# Proto_shield_REV3.net
KiCad netlist of a schematic drawn in EAGLE
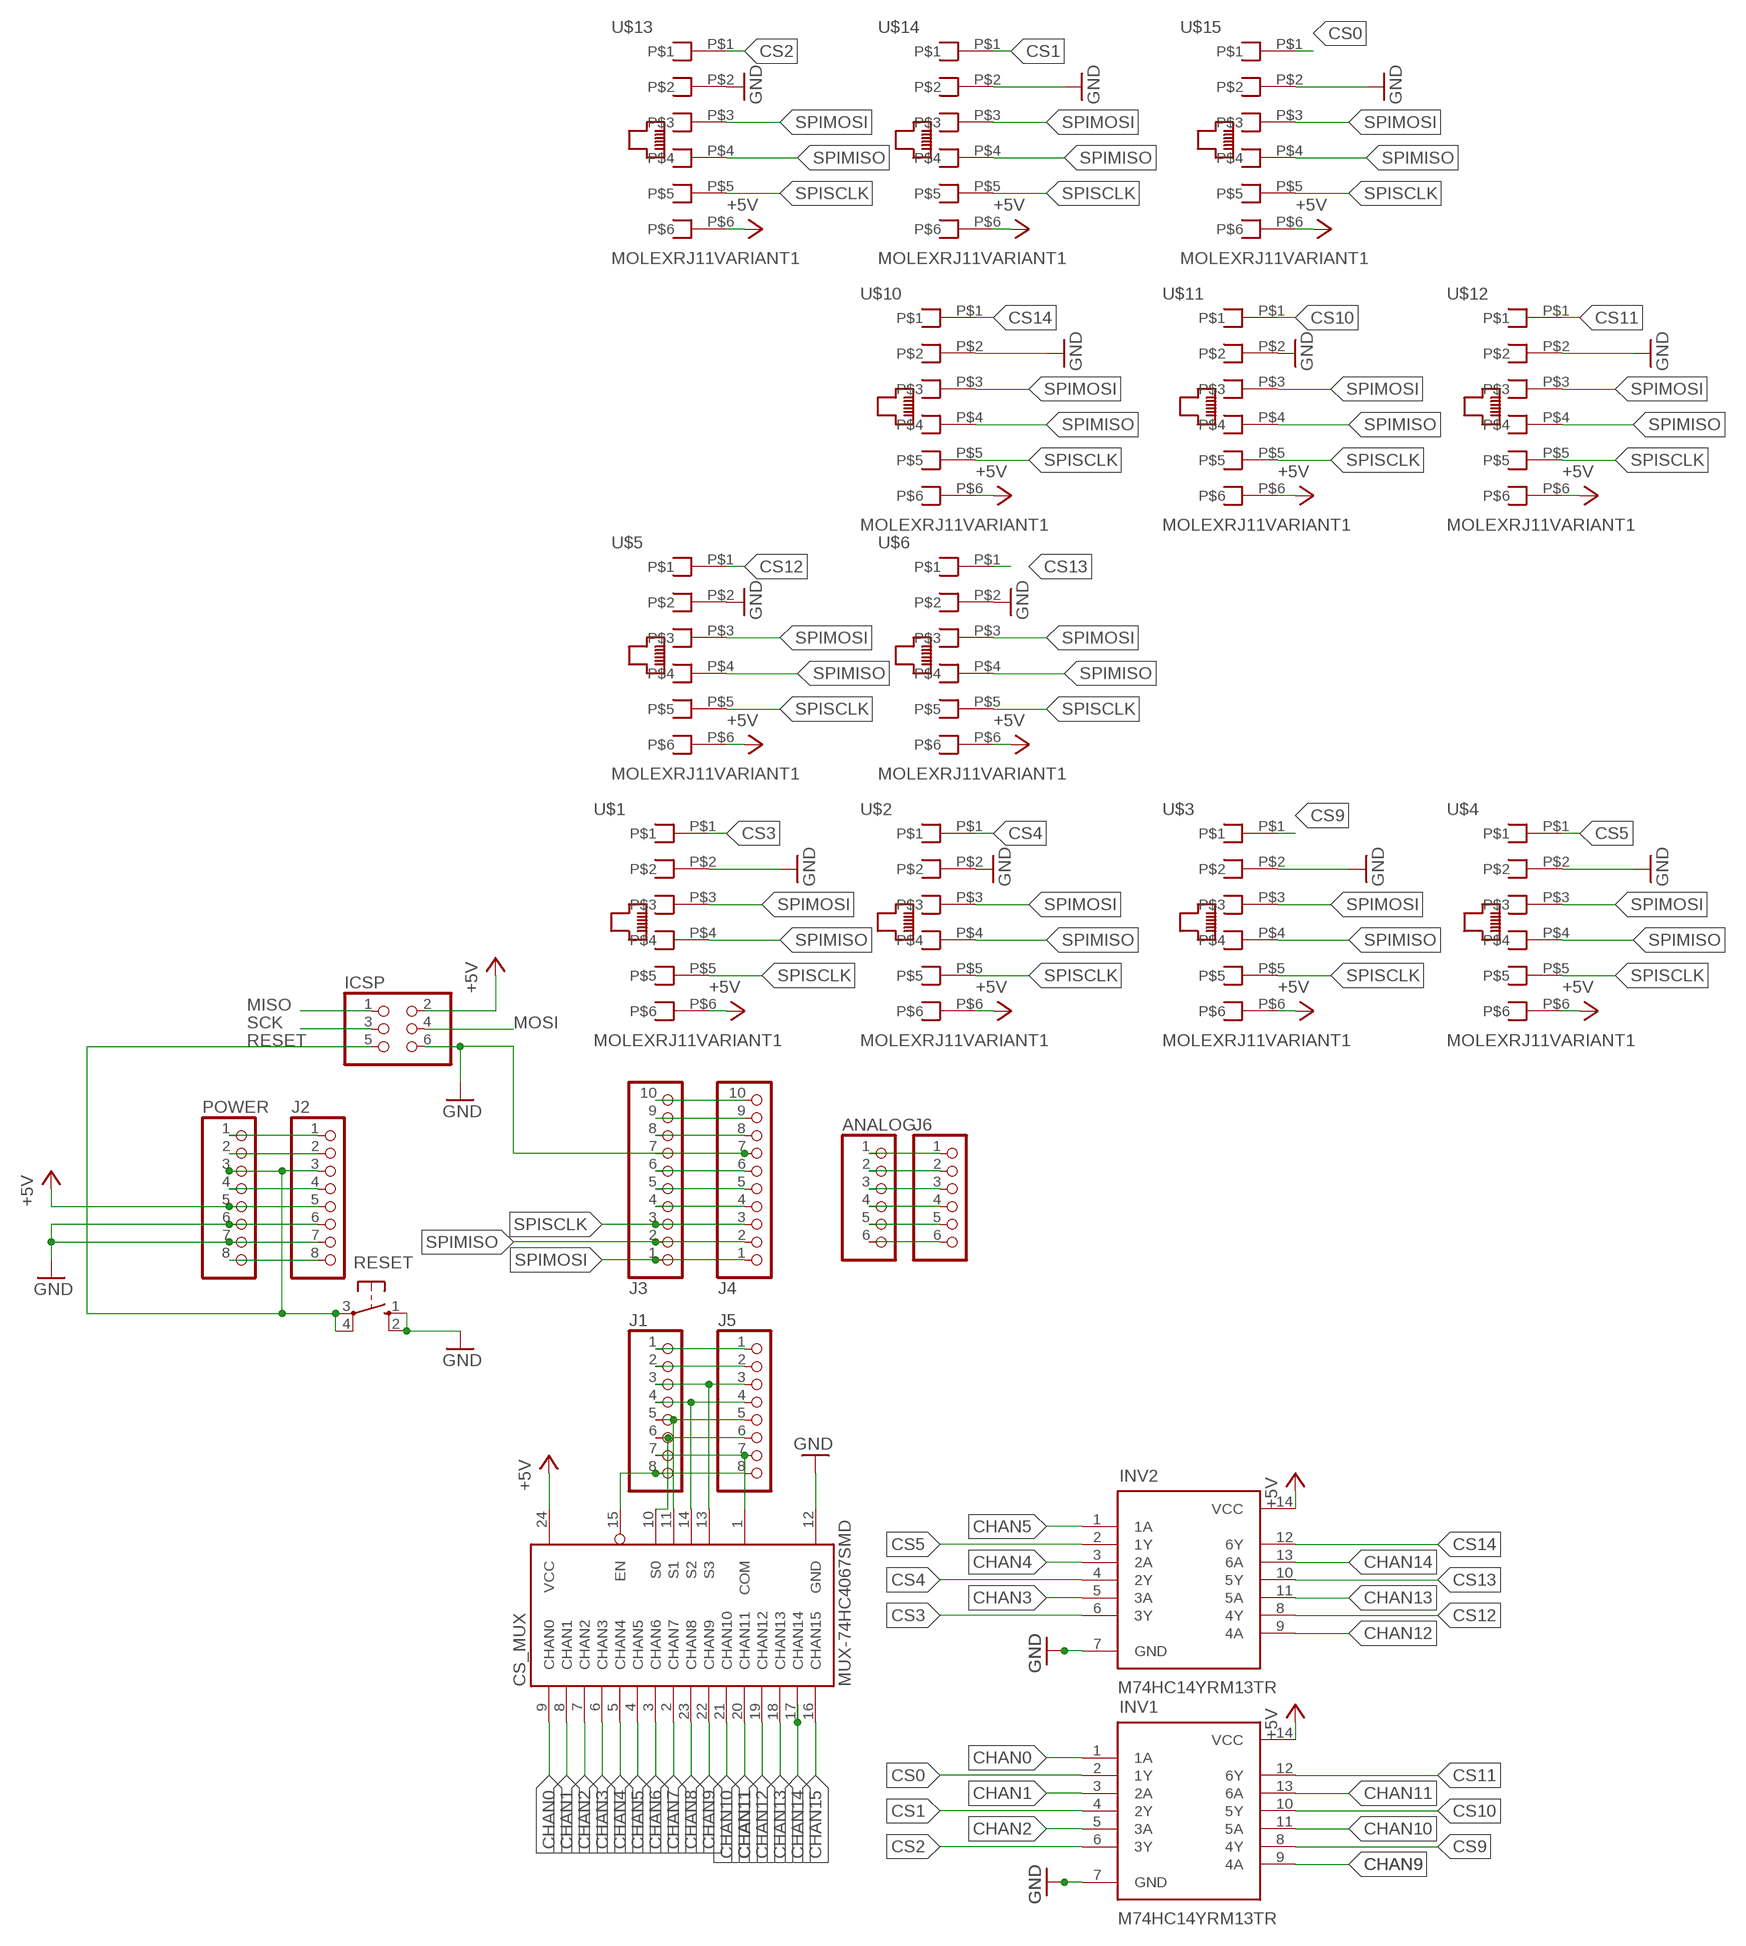
[diagram p0: schematic, sheet 1]

(export (version "E")
  (design (tool "Eeschema 10.0.6"))
  (components
    (comp (ref "ANALOG")
      (value "PINHD-1X6")
      (footprint "eagle-import:1X06")
      (libsource (lib "eagle-import") (part "PINHD-1X6"))
    )
    (comp (ref "CS_MUX")
      (value "MUX-74HC4067SMD")
      (footprint "eagle-import:SSOP24")
      (libsource (lib "eagle-import") (part "MUX-74HC4067SMD"))
    )
    (comp (ref "ICSP")
      (value "PINHD-2X3")
      (footprint "eagle-import:2X03")
      (libsource (lib "eagle-import") (part "PINHD-2X3"))
    )
    (comp (ref "INV1")
      (value "M74HC14YRM13TR")
      (footprint "eagle-import:SO14")
      (libsource (lib "eagle-import") (part "M74HC14YRM13TR"))
    )
    (comp (ref "INV2")
      (value "M74HC14YRM13TR")
      (footprint "eagle-import:SO14")
      (libsource (lib "eagle-import") (part "M74HC14YRM13TR"))
    )
    (comp (ref "J1")
      (value "PINHD-1X8TH")
      (footprint "eagle-import:1X08-TH")
      (libsource (lib "eagle-import") (part "PINHD-1X8TH"))
    )
    (comp (ref "J2")
      (value "PINHD-1X8TH")
      (footprint "eagle-import:1X08-TH")
      (libsource (lib "eagle-import") (part "PINHD-1X8TH"))
    )
    (comp (ref "J3")
      (value "PINHD-1X10TH")
      (footprint "eagle-import:1X10-TH")
      (libsource (lib "eagle-import") (part "PINHD-1X10TH"))
    )
    (comp (ref "J4")
      (value "PINHD-1X10TH")
      (footprint "eagle-import:1X10-TH")
      (libsource (lib "eagle-import") (part "PINHD-1X10TH"))
    )
    (comp (ref "J5")
      (value "PINHD-1X8TH")
      (footprint "eagle-import:1X08-TH")
      (libsource (lib "eagle-import") (part "PINHD-1X8TH"))
    )
    (comp (ref "J6")
      (value "PINHD-1X6")
      (footprint "eagle-import:1X06")
      (libsource (lib "eagle-import") (part "PINHD-1X6"))
    )
    (comp (ref "POWER")
      (value "PINHD-1X8TH")
      (footprint "eagle-import:1X08-TH")
      (libsource (lib "eagle-import") (part "PINHD-1X8TH"))
    )
    (comp (ref "RESET")
      (value "10-XX")
      (footprint "eagle-import:B3F-10XX")
      (libsource (lib "eagle-import") (part "10-XX"))
    )
    (comp (ref "U$1")
      (value "MOLEXRJ11VARIANT1")
      (footprint "eagle-import:RJ11MOLEX")
      (libsource (lib "eagle-import") (part "MOLEXRJ11VARIANT1"))
    )
    (comp (ref "U$2")
      (value "MOLEXRJ11VARIANT1")
      (footprint "eagle-import:RJ11MOLEX")
      (libsource (lib "eagle-import") (part "MOLEXRJ11VARIANT1"))
    )
    (comp (ref "U$3")
      (value "MOLEXRJ11VARIANT1")
      (footprint "eagle-import:RJ11MOLEX")
      (libsource (lib "eagle-import") (part "MOLEXRJ11VARIANT1"))
    )
    (comp (ref "U$4")
      (value "MOLEXRJ11VARIANT1")
      (footprint "eagle-import:RJ11MOLEX")
      (libsource (lib "eagle-import") (part "MOLEXRJ11VARIANT1"))
    )
    (comp (ref "U$5")
      (value "MOLEXRJ11VARIANT1")
      (footprint "eagle-import:RJ11MOLEX")
      (libsource (lib "eagle-import") (part "MOLEXRJ11VARIANT1"))
    )
    (comp (ref "U$6")
      (value "MOLEXRJ11VARIANT1")
      (footprint "eagle-import:RJ11MOLEX")
      (libsource (lib "eagle-import") (part "MOLEXRJ11VARIANT1"))
    )
    (comp (ref "U$10")
      (value "MOLEXRJ11VARIANT1")
      (footprint "eagle-import:RJ11MOLEX")
      (libsource (lib "eagle-import") (part "MOLEXRJ11VARIANT1"))
    )
    (comp (ref "U$11")
      (value "MOLEXRJ11VARIANT1")
      (footprint "eagle-import:RJ11MOLEX")
      (libsource (lib "eagle-import") (part "MOLEXRJ11VARIANT1"))
    )
    (comp (ref "U$12")
      (value "MOLEXRJ11VARIANT1")
      (footprint "eagle-import:RJ11MOLEX")
      (libsource (lib "eagle-import") (part "MOLEXRJ11VARIANT1"))
    )
    (comp (ref "U$13")
      (value "MOLEXRJ11VARIANT1")
      (footprint "eagle-import:RJ11MOLEX")
      (libsource (lib "eagle-import") (part "MOLEXRJ11VARIANT1"))
    )
    (comp (ref "U$14")
      (value "MOLEXRJ11VARIANT1")
      (footprint "eagle-import:RJ11MOLEX")
      (libsource (lib "eagle-import") (part "MOLEXRJ11VARIANT1"))
    )
    (comp (ref "U$15")
      (value "MOLEXRJ11VARIANT1")
      (footprint "eagle-import:RJ11MOLEX")
      (libsource (lib "eagle-import") (part "MOLEXRJ11VARIANT1"))
    )
  )
  (nets
    (net (code "1") (name "+5V") (class "Default")
      (node (ref "CS_MUX") (pin "24") (pinfunction "VCC_24") (pintype "bidirectional"))
      (node (ref "ICSP") (pin "2") (pinfunction "2_2") (pintype "passive"))
      (node (ref "INV1") (pin "14") (pinfunction "VCC_14") (pintype "bidirectional"))
      (node (ref "INV2") (pin "14") (pinfunction "VCC_14") (pintype "bidirectional"))
      (node (ref "J2") (pin "5") (pinfunction "5_5") (pintype "passive"))
      (node (ref "POWER") (pin "5") (pinfunction "5_5") (pintype "passive"))
      (node (ref "U$1") (pin "P$6") (pinfunction "P$6_P$6") (pintype "bidirectional"))
      (node (ref "U$10") (pin "P$6") (pinfunction "P$6_P$6") (pintype "bidirectional"))
      (node (ref "U$11") (pin "P$6") (pinfunction "P$6_P$6") (pintype "bidirectional"))
      (node (ref "U$12") (pin "P$6") (pinfunction "P$6_P$6") (pintype "bidirectional"))
      (node (ref "U$13") (pin "P$6") (pinfunction "P$6_P$6") (pintype "bidirectional"))
      (node (ref "U$14") (pin "P$6") (pinfunction "P$6_P$6") (pintype "bidirectional"))
      (node (ref "U$15") (pin "P$6") (pinfunction "P$6_P$6") (pintype "bidirectional"))
      (node (ref "U$2") (pin "P$6") (pinfunction "P$6_P$6") (pintype "bidirectional"))
      (node (ref "U$3") (pin "P$6") (pinfunction "P$6_P$6") (pintype "bidirectional"))
      (node (ref "U$4") (pin "P$6") (pinfunction "P$6_P$6") (pintype "bidirectional"))
      (node (ref "U$5") (pin "P$6") (pinfunction "P$6_P$6") (pintype "bidirectional"))
      (node (ref "U$6") (pin "P$6") (pinfunction "P$6_P$6") (pintype "bidirectional"))
    )
    (net (code "2") (name "/MISO") (class "Default")
      (node (ref "ICSP") (pin "1") (pinfunction "1_1") (pintype "passive"))
    )
    (net (code "3") (name "/MOSI") (class "Default")
      (node (ref "ICSP") (pin "4") (pinfunction "4_4") (pintype "passive"))
    )
    (net (code "4") (name "/RESET") (class "Default")
      (node (ref "ICSP") (pin "5") (pinfunction "5_5") (pintype "passive"))
      (node (ref "J2") (pin "3") (pinfunction "3_3") (pintype "passive"))
      (node (ref "POWER") (pin "3") (pinfunction "3_3") (pintype "passive"))
      (node (ref "RESET") (pin "3") (pinfunction "P_3") (pintype "passive"))
      (node (ref "RESET") (pin "4") (pinfunction "P1_4") (pintype "passive"))
    )
    (net (code "5") (name "/SCK") (class "Default")
      (node (ref "ICSP") (pin "3") (pinfunction "3_3") (pintype "passive"))
    )
    (net (code "6") (name "CHAN0") (class "Default")
      (node (ref "CS_MUX") (pin "9") (pinfunction "CHAN0_9") (pintype "bidirectional"))
      (node (ref "INV1") (pin "1") (pinfunction "1A_1") (pintype "bidirectional"))
    )
    (net (code "7") (name "CHAN1") (class "Default")
      (node (ref "CS_MUX") (pin "8") (pinfunction "CHAN1_8") (pintype "bidirectional"))
      (node (ref "INV1") (pin "3") (pinfunction "2A_3") (pintype "bidirectional"))
    )
    (net (code "8") (name "CHAN2") (class "Default")
      (node (ref "CS_MUX") (pin "7") (pinfunction "CHAN2_7") (pintype "bidirectional"))
      (node (ref "INV1") (pin "5") (pinfunction "3A_5") (pintype "bidirectional"))
    )
    (net (code "9") (name "CHAN3") (class "Default")
      (node (ref "CS_MUX") (pin "6") (pinfunction "CHAN3_6") (pintype "bidirectional"))
      (node (ref "INV2") (pin "5") (pinfunction "3A_5") (pintype "bidirectional"))
    )
    (net (code "10") (name "CHAN4") (class "Default")
      (node (ref "CS_MUX") (pin "5") (pinfunction "CHAN4_5") (pintype "bidirectional"))
      (node (ref "INV2") (pin "3") (pinfunction "2A_3") (pintype "bidirectional"))
    )
    (net (code "11") (name "CHAN5") (class "Default")
      (node (ref "CS_MUX") (pin "4") (pinfunction "CHAN5_4") (pintype "bidirectional"))
      (node (ref "INV2") (pin "1") (pinfunction "1A_1") (pintype "bidirectional"))
    )
    (net (code "12") (name "CHAN6") (class "Default")
      (node (ref "CS_MUX") (pin "3") (pinfunction "CHAN6_3") (pintype "bidirectional"))
    )
    (net (code "13") (name "CHAN7") (class "Default")
      (node (ref "CS_MUX") (pin "2") (pinfunction "CHAN7_2") (pintype "bidirectional"))
    )
    (net (code "14") (name "CHAN8") (class "Default")
      (node (ref "CS_MUX") (pin "23") (pinfunction "CHAN8_23") (pintype "bidirectional"))
    )
    (net (code "15") (name "CHAN9") (class "Default")
      (node (ref "CS_MUX") (pin "22") (pinfunction "CHAN9_22") (pintype "bidirectional"))
      (node (ref "INV1") (pin "9") (pinfunction "4A_9") (pintype "bidirectional"))
    )
    (net (code "16") (name "CHAN10") (class "Default")
      (node (ref "CS_MUX") (pin "21") (pinfunction "CHAN10_21") (pintype "bidirectional"))
      (node (ref "INV1") (pin "11") (pinfunction "5A_11") (pintype "bidirectional"))
    )
    (net (code "17") (name "CHAN11") (class "Default")
      (node (ref "CS_MUX") (pin "20") (pinfunction "CHAN11_20") (pintype "bidirectional"))
      (node (ref "INV1") (pin "13") (pinfunction "6A_13") (pintype "bidirectional"))
    )
    (net (code "18") (name "CHAN12") (class "Default")
      (node (ref "CS_MUX") (pin "19") (pinfunction "CHAN12_19") (pintype "bidirectional"))
      (node (ref "INV2") (pin "9") (pinfunction "4A_9") (pintype "bidirectional"))
    )
    (net (code "19") (name "CHAN13") (class "Default")
      (node (ref "CS_MUX") (pin "18") (pinfunction "CHAN13_18") (pintype "bidirectional"))
      (node (ref "INV2") (pin "11") (pinfunction "5A_11") (pintype "bidirectional"))
    )
    (net (code "20") (name "CHAN14") (class "Default")
      (node (ref "CS_MUX") (pin "17") (pinfunction "CHAN14_17") (pintype "bidirectional"))
      (node (ref "INV2") (pin "13") (pinfunction "6A_13") (pintype "bidirectional"))
    )
    (net (code "21") (name "CHAN15") (class "Default")
      (node (ref "CS_MUX") (pin "16") (pinfunction "CHAN15_16") (pintype "bidirectional"))
    )
    (net (code "22") (name "CS0") (class "Default")
      (node (ref "INV1") (pin "2") (pinfunction "1Y_2") (pintype "bidirectional"))
      (node (ref "U$15") (pin "P$1") (pinfunction "P$1_P$1") (pintype "bidirectional"))
    )
    (net (code "23") (name "CS1") (class "Default")
      (node (ref "INV1") (pin "4") (pinfunction "2Y_4") (pintype "bidirectional"))
      (node (ref "U$14") (pin "P$1") (pinfunction "P$1_P$1") (pintype "bidirectional"))
    )
    (net (code "24") (name "CS2") (class "Default")
      (node (ref "INV1") (pin "6") (pinfunction "3Y_6") (pintype "bidirectional"))
      (node (ref "U$13") (pin "P$1") (pinfunction "P$1_P$1") (pintype "bidirectional"))
    )
    (net (code "25") (name "CS3") (class "Default")
      (node (ref "INV2") (pin "6") (pinfunction "3Y_6") (pintype "bidirectional"))
      (node (ref "U$1") (pin "P$1") (pinfunction "P$1_P$1") (pintype "bidirectional"))
    )
    (net (code "26") (name "CS4") (class "Default")
      (node (ref "INV2") (pin "4") (pinfunction "2Y_4") (pintype "bidirectional"))
      (node (ref "U$2") (pin "P$1") (pinfunction "P$1_P$1") (pintype "bidirectional"))
    )
    (net (code "27") (name "CS5") (class "Default")
      (node (ref "INV2") (pin "2") (pinfunction "1Y_2") (pintype "bidirectional"))
      (node (ref "U$4") (pin "P$1") (pinfunction "P$1_P$1") (pintype "bidirectional"))
    )
    (net (code "28") (name "CS9") (class "Default")
      (node (ref "INV1") (pin "8") (pinfunction "4Y_8") (pintype "bidirectional"))
      (node (ref "U$3") (pin "P$1") (pinfunction "P$1_P$1") (pintype "bidirectional"))
    )
    (net (code "29") (name "CS10") (class "Default")
      (node (ref "INV1") (pin "10") (pinfunction "5Y_10") (pintype "bidirectional"))
      (node (ref "U$11") (pin "P$1") (pinfunction "P$1_P$1") (pintype "bidirectional"))
    )
    (net (code "30") (name "CS11") (class "Default")
      (node (ref "INV1") (pin "12") (pinfunction "6Y_12") (pintype "bidirectional"))
      (node (ref "U$12") (pin "P$1") (pinfunction "P$1_P$1") (pintype "bidirectional"))
    )
    (net (code "31") (name "CS12") (class "Default")
      (node (ref "INV2") (pin "8") (pinfunction "4Y_8") (pintype "bidirectional"))
      (node (ref "U$5") (pin "P$1") (pinfunction "P$1_P$1") (pintype "bidirectional"))
    )
    (net (code "32") (name "CS13") (class "Default")
      (node (ref "INV2") (pin "10") (pinfunction "5Y_10") (pintype "bidirectional"))
      (node (ref "U$6") (pin "P$1") (pinfunction "P$1_P$1") (pintype "bidirectional"))
    )
    (net (code "33") (name "CS14") (class "Default")
      (node (ref "INV2") (pin "12") (pinfunction "6Y_12") (pintype "bidirectional"))
      (node (ref "U$10") (pin "P$1") (pinfunction "P$1_P$1") (pintype "bidirectional"))
    )
    (net (code "34") (name "GND") (class "Default")
      (node (ref "CS_MUX") (pin "12") (pinfunction "GND_12") (pintype "bidirectional"))
      (node (ref "ICSP") (pin "6") (pinfunction "6_6") (pintype "passive"))
      (node (ref "INV1") (pin "7") (pinfunction "GND_7") (pintype "bidirectional"))
      (node (ref "INV2") (pin "7") (pinfunction "GND_7") (pintype "bidirectional"))
      (node (ref "J2") (pin "7") (pinfunction "7_7") (pintype "passive"))
      (node (ref "J3") (pin "7") (pinfunction "7_7") (pintype "passive"))
      (node (ref "J4") (pin "7") (pinfunction "7_7") (pintype "passive"))
      (node (ref "POWER") (pin "7") (pinfunction "7_7") (pintype "passive"))
      (node (ref "RESET") (pin "1") (pinfunction "S_1") (pintype "passive"))
      (node (ref "RESET") (pin "2") (pinfunction "S1_2") (pintype "passive"))
      (node (ref "U$1") (pin "P$2") (pinfunction "P$2_P$2") (pintype "bidirectional"))
      (node (ref "U$10") (pin "P$2") (pinfunction "P$2_P$2") (pintype "bidirectional"))
      (node (ref "U$11") (pin "P$2") (pinfunction "P$2_P$2") (pintype "bidirectional"))
      (node (ref "U$12") (pin "P$2") (pinfunction "P$2_P$2") (pintype "bidirectional"))
      (node (ref "U$13") (pin "P$2") (pinfunction "P$2_P$2") (pintype "bidirectional"))
      (node (ref "U$14") (pin "P$2") (pinfunction "P$2_P$2") (pintype "bidirectional"))
      (node (ref "U$15") (pin "P$2") (pinfunction "P$2_P$2") (pintype "bidirectional"))
      (node (ref "U$2") (pin "P$2") (pinfunction "P$2_P$2") (pintype "bidirectional"))
      (node (ref "U$3") (pin "P$2") (pinfunction "P$2_P$2") (pintype "bidirectional"))
      (node (ref "U$4") (pin "P$2") (pinfunction "P$2_P$2") (pintype "bidirectional"))
      (node (ref "U$5") (pin "P$2") (pinfunction "P$2_P$2") (pintype "bidirectional"))
      (node (ref "U$6") (pin "P$2") (pinfunction "P$2_P$2") (pintype "bidirectional"))
    )
    (net (code "35") (name "Net-(ANALOG-Pad1)") (class "Default")
      (node (ref "ANALOG") (pin "1") (pinfunction "1_1") (pintype "passive"))
      (node (ref "J6") (pin "1") (pinfunction "1_1") (pintype "passive"))
    )
    (net (code "36") (name "Net-(ANALOG-Pad2)") (class "Default")
      (node (ref "ANALOG") (pin "2") (pinfunction "2_2") (pintype "passive"))
      (node (ref "J6") (pin "2") (pinfunction "2_2") (pintype "passive"))
    )
    (net (code "37") (name "Net-(ANALOG-Pad3)") (class "Default")
      (node (ref "ANALOG") (pin "3") (pinfunction "3_3") (pintype "passive"))
      (node (ref "J6") (pin "3") (pinfunction "3_3") (pintype "passive"))
    )
    (net (code "38") (name "Net-(ANALOG-Pad4)") (class "Default")
      (node (ref "ANALOG") (pin "4") (pinfunction "4_4") (pintype "passive"))
      (node (ref "J6") (pin "4") (pinfunction "4_4") (pintype "passive"))
    )
    (net (code "39") (name "Net-(ANALOG-Pad5)") (class "Default")
      (node (ref "ANALOG") (pin "5") (pinfunction "5_5") (pintype "passive"))
      (node (ref "J6") (pin "5") (pinfunction "5_5") (pintype "passive"))
    )
    (net (code "40") (name "Net-(ANALOG-Pad6)") (class "Default")
      (node (ref "ANALOG") (pin "6") (pinfunction "6_6") (pintype "passive"))
      (node (ref "J6") (pin "6") (pinfunction "6_6") (pintype "passive"))
    )
    (net (code "41") (name "Net-(CS_MUX-COM)") (class "Default")
      (node (ref "CS_MUX") (pin "1") (pinfunction "COM_1") (pintype "bidirectional"))
      (node (ref "J1") (pin "7") (pinfunction "7_7") (pintype "passive"))
      (node (ref "J5") (pin "7") (pinfunction "7_7") (pintype "passive"))
    )
    (net (code "42") (name "Net-(CS_MUX-EN)") (class "Default")
      (node (ref "CS_MUX") (pin "15") (pinfunction "EN_15") (pintype "input"))
      (node (ref "J1") (pin "8") (pinfunction "8_8") (pintype "passive"))
      (node (ref "J5") (pin "8") (pinfunction "8_8") (pintype "passive"))
    )
    (net (code "43") (name "Net-(CS_MUX-S0)") (class "Default")
      (node (ref "CS_MUX") (pin "10") (pinfunction "S0_10") (pintype "input"))
      (node (ref "J1") (pin "6") (pinfunction "6_6") (pintype "passive"))
      (node (ref "J5") (pin "6") (pinfunction "6_6") (pintype "passive"))
    )
    (net (code "44") (name "Net-(CS_MUX-S1)") (class "Default")
      (node (ref "CS_MUX") (pin "11") (pinfunction "S1_11") (pintype "input"))
      (node (ref "J1") (pin "5") (pinfunction "5_5") (pintype "passive"))
      (node (ref "J5") (pin "5") (pinfunction "5_5") (pintype "passive"))
    )
    (net (code "45") (name "Net-(CS_MUX-S2)") (class "Default")
      (node (ref "CS_MUX") (pin "14") (pinfunction "S2_14") (pintype "input"))
      (node (ref "J1") (pin "4") (pinfunction "4_4") (pintype "passive"))
      (node (ref "J5") (pin "4") (pinfunction "4_4") (pintype "passive"))
    )
    (net (code "46") (name "Net-(CS_MUX-S3)") (class "Default")
      (node (ref "CS_MUX") (pin "13") (pinfunction "S3_13") (pintype "input"))
      (node (ref "J1") (pin "3") (pinfunction "3_3") (pintype "passive"))
      (node (ref "J5") (pin "3") (pinfunction "3_3") (pintype "passive"))
    )
    (net (code "47") (name "Net-(J1-Pad1)") (class "Default")
      (node (ref "J1") (pin "1") (pinfunction "1_1") (pintype "passive"))
      (node (ref "J5") (pin "1") (pinfunction "1_1") (pintype "passive"))
    )
    (net (code "48") (name "Net-(J1-Pad2)") (class "Default")
      (node (ref "J1") (pin "2") (pinfunction "2_2") (pintype "passive"))
      (node (ref "J5") (pin "2") (pinfunction "2_2") (pintype "passive"))
    )
    (net (code "49") (name "Net-(J2-Pad1)") (class "Default")
      (node (ref "J2") (pin "1") (pinfunction "1_1") (pintype "passive"))
      (node (ref "POWER") (pin "1") (pinfunction "1_1") (pintype "passive"))
    )
    (net (code "50") (name "Net-(J2-Pad2)") (class "Default")
      (node (ref "J2") (pin "2") (pinfunction "2_2") (pintype "passive"))
      (node (ref "POWER") (pin "2") (pinfunction "2_2") (pintype "passive"))
    )
    (net (code "51") (name "Net-(J2-Pad4)") (class "Default")
      (node (ref "J2") (pin "4") (pinfunction "4_4") (pintype "passive"))
      (node (ref "POWER") (pin "4") (pinfunction "4_4") (pintype "passive"))
    )
    (net (code "52") (name "Net-(J2-Pad6)") (class "Default")
      (node (ref "J2") (pin "6") (pinfunction "6_6") (pintype "passive"))
      (node (ref "POWER") (pin "6") (pinfunction "6_6") (pintype "passive"))
    )
    (net (code "53") (name "Net-(J2-Pad8)") (class "Default")
      (node (ref "J2") (pin "8") (pinfunction "8_8") (pintype "passive"))
      (node (ref "POWER") (pin "8") (pinfunction "8_8") (pintype "passive"))
    )
    (net (code "54") (name "Net-(J3-Pad4)") (class "Default")
      (node (ref "J3") (pin "4") (pinfunction "4_4") (pintype "passive"))
      (node (ref "J4") (pin "4") (pinfunction "4_4") (pintype "passive"))
    )
    (net (code "55") (name "Net-(J3-Pad5)") (class "Default")
      (node (ref "J3") (pin "5") (pinfunction "5_5") (pintype "passive"))
      (node (ref "J4") (pin "5") (pinfunction "5_5") (pintype "passive"))
    )
    (net (code "56") (name "Net-(J3-Pad6)") (class "Default")
      (node (ref "J3") (pin "6") (pinfunction "6_6") (pintype "passive"))
      (node (ref "J4") (pin "6") (pinfunction "6_6") (pintype "passive"))
    )
    (net (code "57") (name "Net-(J3-Pad8)") (class "Default")
      (node (ref "J3") (pin "8") (pinfunction "8_8") (pintype "passive"))
      (node (ref "J4") (pin "8") (pinfunction "8_8") (pintype "passive"))
    )
    (net (code "58") (name "Net-(J3-Pad9)") (class "Default")
      (node (ref "J3") (pin "9") (pinfunction "9_9") (pintype "passive"))
      (node (ref "J4") (pin "9") (pinfunction "9_9") (pintype "passive"))
    )
    (net (code "59") (name "Net-(J3-Pad10)") (class "Default")
      (node (ref "J3") (pin "10") (pinfunction "10_10") (pintype "passive"))
      (node (ref "J4") (pin "10") (pinfunction "10_10") (pintype "passive"))
    )
    (net (code "60") (name "SPIMISO") (class "Default")
      (node (ref "J3") (pin "2") (pinfunction "2_2") (pintype "passive"))
      (node (ref "J4") (pin "2") (pinfunction "2_2") (pintype "passive"))
      (node (ref "U$1") (pin "P$4") (pinfunction "P$4_P$4") (pintype "bidirectional"))
      (node (ref "U$10") (pin "P$4") (pinfunction "P$4_P$4") (pintype "bidirectional"))
      (node (ref "U$11") (pin "P$4") (pinfunction "P$4_P$4") (pintype "bidirectional"))
      (node (ref "U$12") (pin "P$4") (pinfunction "P$4_P$4") (pintype "bidirectional"))
      (node (ref "U$13") (pin "P$4") (pinfunction "P$4_P$4") (pintype "bidirectional"))
      (node (ref "U$14") (pin "P$4") (pinfunction "P$4_P$4") (pintype "bidirectional"))
      (node (ref "U$15") (pin "P$4") (pinfunction "P$4_P$4") (pintype "bidirectional"))
      (node (ref "U$2") (pin "P$4") (pinfunction "P$4_P$4") (pintype "bidirectional"))
      (node (ref "U$3") (pin "P$4") (pinfunction "P$4_P$4") (pintype "bidirectional"))
      (node (ref "U$4") (pin "P$4") (pinfunction "P$4_P$4") (pintype "bidirectional"))
      (node (ref "U$5") (pin "P$4") (pinfunction "P$4_P$4") (pintype "bidirectional"))
      (node (ref "U$6") (pin "P$4") (pinfunction "P$4_P$4") (pintype "bidirectional"))
    )
    (net (code "61") (name "SPIMOSI") (class "Default")
      (node (ref "J3") (pin "1") (pinfunction "1_1") (pintype "passive"))
      (node (ref "J4") (pin "1") (pinfunction "1_1") (pintype "passive"))
      (node (ref "U$1") (pin "P$3") (pinfunction "P$3_P$3") (pintype "bidirectional"))
      (node (ref "U$10") (pin "P$3") (pinfunction "P$3_P$3") (pintype "bidirectional"))
      (node (ref "U$11") (pin "P$3") (pinfunction "P$3_P$3") (pintype "bidirectional"))
      (node (ref "U$12") (pin "P$3") (pinfunction "P$3_P$3") (pintype "bidirectional"))
      (node (ref "U$13") (pin "P$3") (pinfunction "P$3_P$3") (pintype "bidirectional"))
      (node (ref "U$14") (pin "P$3") (pinfunction "P$3_P$3") (pintype "bidirectional"))
      (node (ref "U$15") (pin "P$3") (pinfunction "P$3_P$3") (pintype "bidirectional"))
      (node (ref "U$2") (pin "P$3") (pinfunction "P$3_P$3") (pintype "bidirectional"))
      (node (ref "U$3") (pin "P$3") (pinfunction "P$3_P$3") (pintype "bidirectional"))
      (node (ref "U$4") (pin "P$3") (pinfunction "P$3_P$3") (pintype "bidirectional"))
      (node (ref "U$5") (pin "P$3") (pinfunction "P$3_P$3") (pintype "bidirectional"))
      (node (ref "U$6") (pin "P$3") (pinfunction "P$3_P$3") (pintype "bidirectional"))
    )
    (net (code "62") (name "SPISCLK") (class "Default")
      (node (ref "J3") (pin "3") (pinfunction "3_3") (pintype "passive"))
      (node (ref "J4") (pin "3") (pinfunction "3_3") (pintype "passive"))
      (node (ref "U$1") (pin "P$5") (pinfunction "P$5_P$5") (pintype "bidirectional"))
      (node (ref "U$10") (pin "P$5") (pinfunction "P$5_P$5") (pintype "bidirectional"))
      (node (ref "U$11") (pin "P$5") (pinfunction "P$5_P$5") (pintype "bidirectional"))
      (node (ref "U$12") (pin "P$5") (pinfunction "P$5_P$5") (pintype "bidirectional"))
      (node (ref "U$13") (pin "P$5") (pinfunction "P$5_P$5") (pintype "bidirectional"))
      (node (ref "U$14") (pin "P$5") (pinfunction "P$5_P$5") (pintype "bidirectional"))
      (node (ref "U$15") (pin "P$5") (pinfunction "P$5_P$5") (pintype "bidirectional"))
      (node (ref "U$2") (pin "P$5") (pinfunction "P$5_P$5") (pintype "bidirectional"))
      (node (ref "U$3") (pin "P$5") (pinfunction "P$5_P$5") (pintype "bidirectional"))
      (node (ref "U$4") (pin "P$5") (pinfunction "P$5_P$5") (pintype "bidirectional"))
      (node (ref "U$5") (pin "P$5") (pinfunction "P$5_P$5") (pintype "bidirectional"))
      (node (ref "U$6") (pin "P$5") (pinfunction "P$5_P$5") (pintype "bidirectional"))
    )
  )
)
